# hardware-ble-led-driver-ws2812.net
KiCad netlist of a schematic drawn in EAGLE
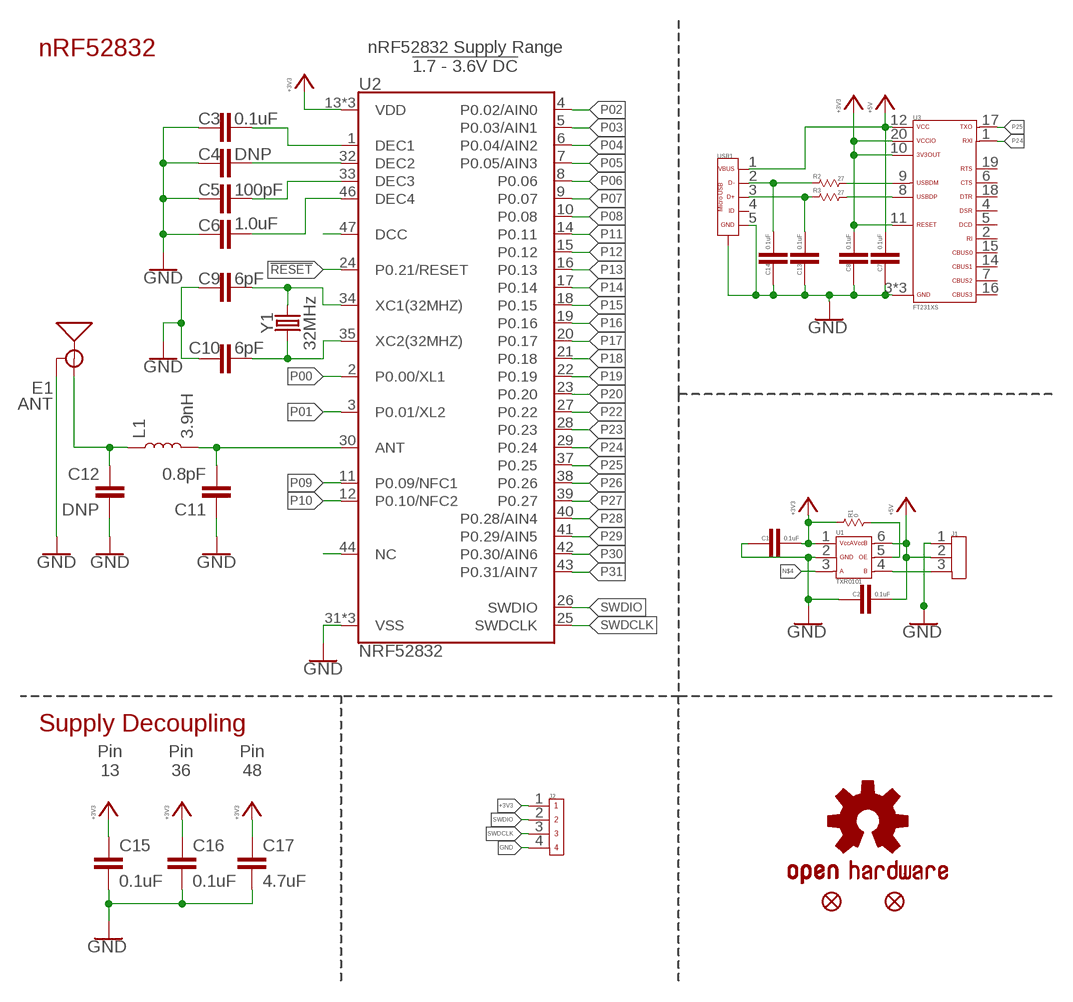
[diagram p0: schematic, sheet 1]

(export (version "E")
  (design (tool "Eeschema 10.0.6"))
  (components
    (comp (ref "C1")
      (value "0.1uF")
      (footprint "eagle-import:0402")
      (libsource (lib "eagle-import") (part "0.1UF-0402-16V-10%"))
    )
    (comp (ref "C2")
      (value "0.1uF")
      (footprint "eagle-import:0402")
      (libsource (lib "eagle-import") (part "0.1UF-0402-16V-10%"))
    )
    (comp (ref "C3")
      (value "0.1uF")
      (footprint "eagle-import:0402")
      (libsource (lib "eagle-import") (part "0.1UF-0402-16V-10%"))
    )
    (comp (ref "C4")
      (value "DNP")
      (footprint "eagle-import:0402")
      (libsource (lib "eagle-import") (part "CAP0402"))
    )
    (comp (ref "C5")
      (value "100pF")
      (footprint "eagle-import:0402")
      (libsource (lib "eagle-import") (part "100PF-0402-50V-5%"))
    )
    (comp (ref "C6")
      (value "1.0uF")
      (footprint "eagle-import:0402")
      (libsource (lib "eagle-import") (part "1.0UF-0402-16V-10%"))
    )
    (comp (ref "C7")
      (value "0.1uF")
      (footprint "eagle-import:0402")
      (libsource (lib "eagle-import") (part "0.1UF-0402-16V-10%"))
    )
    (comp (ref "C8")
      (value "0.1uF")
      (footprint "eagle-import:0402")
      (libsource (lib "eagle-import") (part "0.1UF-0402-16V-10%"))
    )
    (comp (ref "C9")
      (value "6pF")
      (footprint "eagle-import:0402")
      (libsource (lib "eagle-import") (part "6PF-0402-50V-0.5%"))
    )
    (comp (ref "C10")
      (value "6pF")
      (footprint "eagle-import:0402")
      (libsource (lib "eagle-import") (part "6PF-0402-50V-0.5%"))
    )
    (comp (ref "C11")
      (value "0.8pF")
      (footprint "eagle-import:0402")
      (libsource (lib "eagle-import") (part "0.8PF-0402-50V-0.1PF"))
    )
    (comp (ref "C12")
      (value "DNP")
      (footprint "eagle-import:0402")
      (libsource (lib "eagle-import") (part "CAP0402"))
    )
    (comp (ref "C13")
      (value "0.1uF")
      (footprint "eagle-import:0402")
      (libsource (lib "eagle-import") (part "0.1UF-0402-16V-10%"))
    )
    (comp (ref "C14")
      (value "0.1uF")
      (footprint "eagle-import:0402")
      (libsource (lib "eagle-import") (part "0.1UF-0402-16V-10%"))
    )
    (comp (ref "C15")
      (value "0.1uF")
      (footprint "eagle-import:0402")
      (libsource (lib "eagle-import") (part "0.1UF-0402-16V-10%"))
    )
    (comp (ref "C16")
      (value "0.1uF")
      (footprint "eagle-import:0402")
      (libsource (lib "eagle-import") (part "0.1UF-0402-16V-10%"))
    )
    (comp (ref "C17")
      (value "4.7uF")
      (footprint "eagle-import:0603")
      (libsource (lib "eagle-import") (part "4.7UF0603"))
    )
    (comp (ref "E1")
      (value "ANT")
      (footprint "eagle-import:TRACE_ANTENNA_2.4GHZ_15.2MM")
      (libsource (lib "eagle-import") (part "ANTENNA-GROUNDEDTRACE-15.2MM"))
    )
    (comp (ref "FD1")
      (value "FIDUCIALUFIDUCIAL")
      (footprint "eagle-import:FIDUCIAL-MICRO")
      (libsource (lib "eagle-import") (part "FIDUCIALUFIDUCIAL"))
    )
    (comp (ref "FD2")
      (value "FIDUCIALUFIDUCIAL")
      (footprint "eagle-import:FIDUCIAL-MICRO")
      (libsource (lib "eagle-import") (part "FIDUCIALUFIDUCIAL"))
    )
    (comp (ref "J1")
      (value "3PIN_HEADER_PITCH2.54MM_TH")
      (footprint "eagle-import:3PIN_HEADER_PITCH2.54MM_TH")
      (libsource (lib "eagle-import") (part "3PIN_HEADER_PITCH2.54MM_TH"))
    )
    (comp (ref "J2")
      (value "4PIN_HEADER_PITCH1.27MM_TH")
      (footprint "eagle-import:4PIN_HEADER_PITCH1.27MM_TH")
      (libsource (lib "eagle-import") (part "4PIN_HEADER_PITCH1.27MM_TH"))
    )
    (comp (ref "L1")
      (value "3.9nH")
      (footprint "eagle-import:0402")
      (libsource (lib "eagle-import") (part "INDUCTOR-0402-3.9NH"))
    )
    (comp (ref "LOGO1")
      (value "OSHW-LOGOMINI")
      (footprint "eagle-import:OSHW-LOGO-MINI")
      (libsource (lib "eagle-import") (part "OSHW-LOGOMINI"))
    )
    (comp (ref "R1")
      (value "0")
      (footprint "eagle-import:0402")
      (libsource (lib "eagle-import") (part "RESISTOR_0402"))
    )
    (comp (ref "R2")
      (value "27")
      (footprint "eagle-import:0402")
      (libsource (lib "eagle-import") (part "RESISTOR_0402"))
    )
    (comp (ref "R3")
      (value "27")
      (footprint "eagle-import:0402")
      (libsource (lib "eagle-import") (part "RESISTOR_0402"))
    )
    (comp (ref "U1")
      (value "TXB0101-DCK")
      (footprint "eagle-import:TSSOP-6")
      (libsource (lib "eagle-import") (part "TXB0101-DCK"))
    )
    (comp (ref "U2")
      (value "NRF52832")
      (footprint "eagle-import:QFN48-6X6MM")
      (libsource (lib "eagle-import") (part "NRF52832"))
    )
    (comp (ref "U3")
      (value "FT231XS_WFQFN20")
      (footprint "eagle-import:WFQFN-20")
      (libsource (lib "eagle-import") (part "FT231XS_WFQFN20"))
    )
    (comp (ref "USB1")
      (value "USB-2.0-MICRO_SMD_SMD")
      (footprint "eagle-import:MICRO-USB-B-SMD-SMD")
      (libsource (lib "eagle-import") (part "USB-2.0-MICRO_SMD_SMD"))
    )
    (comp (ref "Y1")
      (value "32MHz")
      (footprint "eagle-import:CRYSTAL-SMD-2.0X1.6MM")
      (libsource (lib "eagle-import") (part "CRYSTAL-32MHZ-SMD-2.0X1.6MM"))
    )
  )
  (nets
    (net (code "1") (name "+3V3") (class "Default")
      (node (ref "C1") (pin "2") (pinfunction "2_2") (pintype "passive"))
      (node (ref "C15") (pin "1") (pinfunction "1_1") (pintype "passive"))
      (node (ref "C16") (pin "1") (pinfunction "1_1") (pintype "passive"))
      (node (ref "C17") (pin "1") (pinfunction "1_1") (pintype "passive"))
      (node (ref "C8") (pin "2") (pinfunction "2_2") (pintype "passive"))
      (node (ref "J2") (pin "1") (pinfunction "1_1") (pintype "passive"))
      (node (ref "R1") (pin "1") (pinfunction "1_1") (pintype "passive"))
      (node (ref "U1") (pin "1") (pinfunction "1_1") (pintype "passive"))
      (node (ref "U2") (pin "13") (pinfunction "VDD_13") (pintype "bidirectional"))
      (node (ref "U2") (pin "36") (pinfunction "VDD_36") (pintype "bidirectional"))
      (node (ref "U2") (pin "48") (pinfunction "VDD_48") (pintype "bidirectional"))
      (node (ref "U3") (pin "10") (pinfunction "3V3OUT_10") (pintype "passive"))
      (node (ref "U3") (pin "11") (pinfunction "RESET_11") (pintype "passive"))
      (node (ref "U3") (pin "20") (pinfunction "VCCIO_20") (pintype "passive"))
    )
    (net (code "2") (name "+5V") (class "Default")
      (node (ref "C2") (pin "2") (pinfunction "2_2") (pintype "passive"))
      (node (ref "C7") (pin "2") (pinfunction "2_2") (pintype "passive"))
      (node (ref "J1") (pin "2") (pinfunction "2_2") (pintype "passive"))
      (node (ref "U1") (pin "6") (pinfunction "6_6") (pintype "passive"))
      (node (ref "U3") (pin "12") (pinfunction "VCC_12") (pintype "passive"))
      (node (ref "USB1") (pin "1") (pinfunction "VBUS_1") (pintype "passive"))
    )
    (net (code "3") (name "/~{RESET}") (class "Default")
      (node (ref "U2") (pin "24") (pinfunction "P0.21/RESET_24") (pintype "bidirectional"))
    )
    (net (code "4") (name "GND") (class "Default")
      (node (ref "C1") (pin "1") (pinfunction "1_1") (pintype "passive"))
      (node (ref "C10") (pin "2") (pinfunction "2_2") (pintype "passive"))
      (node (ref "C11") (pin "1") (pinfunction "1_1") (pintype "passive"))
      (node (ref "C12") (pin "2") (pinfunction "2_2") (pintype "passive"))
      (node (ref "C13") (pin "1") (pinfunction "1_1") (pintype "passive"))
      (node (ref "C14") (pin "1") (pinfunction "1_1") (pintype "passive"))
      (node (ref "C15") (pin "2") (pinfunction "2_2") (pintype "passive"))
      (node (ref "C16") (pin "2") (pinfunction "2_2") (pintype "passive"))
      (node (ref "C17") (pin "2") (pinfunction "2_2") (pintype "passive"))
      (node (ref "C2") (pin "1") (pinfunction "1_1") (pintype "passive"))
      (node (ref "C3") (pin "1") (pinfunction "1_1") (pintype "passive"))
      (node (ref "C4") (pin "1") (pinfunction "1_1") (pintype "passive"))
      (node (ref "C5") (pin "1") (pinfunction "1_1") (pintype "passive"))
      (node (ref "C6") (pin "1") (pinfunction "1_1") (pintype "passive"))
      (node (ref "C7") (pin "1") (pinfunction "1_1") (pintype "passive"))
      (node (ref "C8") (pin "1") (pinfunction "1_1") (pintype "passive"))
      (node (ref "C9") (pin "1") (pinfunction "1_1") (pintype "passive"))
      (node (ref "E1") (pin "GND") (pinfunction "GND_GND") (pintype "bidirectional"))
      (node (ref "J1") (pin "1") (pinfunction "1_1") (pintype "passive"))
      (node (ref "J2") (pin "4") (pinfunction "4_4") (pintype "passive"))
      (node (ref "U1") (pin "2") (pinfunction "2_2") (pintype "passive"))
      (node (ref "U2") (pin "31") (pinfunction "VSS_31") (pintype "bidirectional"))
      (node (ref "U2") (pin "45") (pinfunction "VSS_45") (pintype "bidirectional"))
      (node (ref "U2") (pin "EP") (pinfunction "VSS_EP") (pintype "bidirectional"))
      (node (ref "U3") (pin "13") (pinfunction "GND_13") (pintype "passive"))
      (node (ref "U3") (pin "3") (pinfunction "GND_3") (pintype "passive"))
      (node (ref "U3") (pin "T") (pinfunction "GND_T") (pintype "passive"))
      (node (ref "USB1") (pin "5") (pinfunction "GND_5") (pintype "passive"))
      (node (ref "USB1") (pin "M1") (pinfunction "SHIELD_M1") (pintype "passive"))
      (node (ref "USB1") (pin "M2") (pinfunction "SHIELD_M2") (pintype "passive"))
      (node (ref "USB1") (pin "M3") (pinfunction "SHIELD_M3") (pintype "passive"))
      (node (ref "USB1") (pin "M4") (pinfunction "SHIELD_M4") (pintype "passive"))
      (node (ref "USB1") (pin "S1") (pinfunction "SHIELD_S1") (pintype "passive"))
      (node (ref "USB1") (pin "S2") (pinfunction "SHIELD_S2") (pintype "passive"))
    )
    (net (code "5") (name "N$4") (class "Default")
      (node (ref "U1") (pin "3") (pinfunction "3_3") (pintype "passive"))
    )
    (net (code "6") (name "Net-(E1-SIGNAL)") (class "Default")
      (node (ref "C12") (pin "1") (pinfunction "1_1") (pintype "passive"))
      (node (ref "E1") (pin "ANT") (pinfunction "SIGNAL_ANT") (pintype "bidirectional"))
      (node (ref "L1") (pin "1") (pinfunction "1_1") (pintype "passive"))
    )
    (net (code "7") (name "Net-(J1-Pad3)") (class "Default")
      (node (ref "J1") (pin "3") (pinfunction "3_3") (pintype "passive"))
      (node (ref "U1") (pin "4") (pinfunction "4_4") (pintype "passive"))
    )
    (net (code "8") (name "Net-(R1-Pad2)") (class "Default")
      (node (ref "R1") (pin "2") (pinfunction "2_2") (pintype "passive"))
      (node (ref "U1") (pin "5") (pinfunction "5_5") (pintype "passive"))
    )
    (net (code "9") (name "Net-(U2-ANT)") (class "Default")
      (node (ref "C11") (pin "2") (pinfunction "2_2") (pintype "passive"))
      (node (ref "L1") (pin "2") (pinfunction "2_2") (pintype "passive"))
      (node (ref "U2") (pin "30") (pinfunction "ANT_30") (pintype "bidirectional"))
    )
    (net (code "10") (name "Net-(U2-DEC1)") (class "Default")
      (node (ref "C3") (pin "2") (pinfunction "2_2") (pintype "passive"))
      (node (ref "U2") (pin "1") (pinfunction "DEC1_1") (pintype "bidirectional"))
    )
    (net (code "11") (name "Net-(U2-DEC2)") (class "Default")
      (node (ref "C4") (pin "2") (pinfunction "2_2") (pintype "passive"))
      (node (ref "U2") (pin "32") (pinfunction "DEC2_32") (pintype "bidirectional"))
    )
    (net (code "12") (name "Net-(U2-DEC3)") (class "Default")
      (node (ref "C5") (pin "2") (pinfunction "2_2") (pintype "passive"))
      (node (ref "U2") (pin "33") (pinfunction "DEC3_33") (pintype "bidirectional"))
    )
    (net (code "13") (name "Net-(U2-DEC4)") (class "Default")
      (node (ref "C6") (pin "2") (pinfunction "2_2") (pintype "passive"))
      (node (ref "U2") (pin "46") (pinfunction "DEC4_46") (pintype "bidirectional"))
    )
    (net (code "14") (name "Net-(U2-XC1(32MHZ))") (class "Default")
      (node (ref "C9") (pin "2") (pinfunction "2_2") (pintype "passive"))
      (node (ref "U2") (pin "34") (pinfunction "XC1(32MHZ)_34") (pintype "bidirectional"))
      (node (ref "Y1") (pin "3") (pinfunction "2_3") (pintype "passive"))
    )
    (net (code "15") (name "Net-(U2-XC2(32MHZ))") (class "Default")
      (node (ref "C10") (pin "1") (pinfunction "1_1") (pintype "passive"))
      (node (ref "U2") (pin "35") (pinfunction "XC2(32MHZ)_35") (pintype "bidirectional"))
      (node (ref "Y1") (pin "1") (pinfunction "1_1") (pintype "passive"))
    )
    (net (code "16") (name "Net-(U3-USBDM)") (class "Default")
      (node (ref "R2") (pin "2") (pinfunction "2_2") (pintype "passive"))
      (node (ref "U3") (pin "9") (pinfunction "USBDM_9") (pintype "passive"))
    )
    (net (code "17") (name "Net-(U3-USBDP)") (class "Default")
      (node (ref "R3") (pin "2") (pinfunction "2_2") (pintype "passive"))
      (node (ref "U3") (pin "8") (pinfunction "USBDP_8") (pintype "passive"))
    )
    (net (code "18") (name "Net-(USB1-D+)") (class "Default")
      (node (ref "C13") (pin "2") (pinfunction "2_2") (pintype "passive"))
      (node (ref "R3") (pin "1") (pinfunction "1_1") (pintype "passive"))
      (node (ref "USB1") (pin "3") (pinfunction "D+_3") (pintype "passive"))
    )
    (net (code "19") (name "Net-(USB1-D-)") (class "Default")
      (node (ref "C14") (pin "2") (pinfunction "2_2") (pintype "passive"))
      (node (ref "R2") (pin "1") (pinfunction "1_1") (pintype "passive"))
      (node (ref "USB1") (pin "2") (pinfunction "D-_2") (pintype "passive"))
    )
    (net (code "20") (name "P00") (class "Default")
      (node (ref "U2") (pin "2") (pinfunction "P0.00/XL1_2") (pintype "bidirectional"))
    )
    (net (code "21") (name "P01") (class "Default")
      (node (ref "U2") (pin "3") (pinfunction "P0.01/XL2_3") (pintype "bidirectional"))
    )
    (net (code "22") (name "P02") (class "Default")
      (node (ref "U2") (pin "4") (pinfunction "P0.02/AIN0_4") (pintype "bidirectional"))
    )
    (net (code "23") (name "P03") (class "Default")
      (node (ref "U2") (pin "5") (pinfunction "P0.03/AIN1_5") (pintype "bidirectional"))
    )
    (net (code "24") (name "P04") (class "Default")
      (node (ref "U2") (pin "6") (pinfunction "P0.04/AIN2_6") (pintype "bidirectional"))
    )
    (net (code "25") (name "P05") (class "Default")
      (node (ref "U2") (pin "7") (pinfunction "P0.05/AIN3_7") (pintype "bidirectional"))
    )
    (net (code "26") (name "P06") (class "Default")
      (node (ref "U2") (pin "8") (pinfunction "P0.06_8") (pintype "bidirectional"))
    )
    (net (code "27") (name "P07") (class "Default")
      (node (ref "U2") (pin "9") (pinfunction "P0.07_9") (pintype "bidirectional"))
    )
    (net (code "28") (name "P08") (class "Default")
      (node (ref "U2") (pin "10") (pinfunction "P0.08_10") (pintype "bidirectional"))
    )
    (net (code "29") (name "P09") (class "Default")
      (node (ref "U2") (pin "11") (pinfunction "P0.09/NFC1_11") (pintype "bidirectional"))
    )
    (net (code "30") (name "P10") (class "Default")
      (node (ref "U2") (pin "12") (pinfunction "P0.10/NFC2_12") (pintype "bidirectional"))
    )
    (net (code "31") (name "P11") (class "Default")
      (node (ref "U2") (pin "14") (pinfunction "P0.11_14") (pintype "bidirectional"))
    )
    (net (code "32") (name "P12") (class "Default")
      (node (ref "U2") (pin "15") (pinfunction "P0.12_15") (pintype "bidirectional"))
    )
    (net (code "33") (name "P13") (class "Default")
      (node (ref "U2") (pin "16") (pinfunction "P0.13_16") (pintype "bidirectional"))
    )
    (net (code "34") (name "P14") (class "Default")
      (node (ref "U2") (pin "17") (pinfunction "P0.14_17") (pintype "bidirectional"))
    )
    (net (code "35") (name "P15") (class "Default")
      (node (ref "U2") (pin "18") (pinfunction "P0.15_18") (pintype "bidirectional"))
    )
    (net (code "36") (name "P16") (class "Default")
      (node (ref "U2") (pin "19") (pinfunction "P0.16_19") (pintype "bidirectional"))
    )
    (net (code "37") (name "P17") (class "Default")
      (node (ref "U2") (pin "20") (pinfunction "P0.17_20") (pintype "bidirectional"))
    )
    (net (code "38") (name "P18") (class "Default")
      (node (ref "U2") (pin "21") (pinfunction "P0.18_21") (pintype "bidirectional"))
    )
    (net (code "39") (name "P19") (class "Default")
      (node (ref "U2") (pin "22") (pinfunction "P0.19_22") (pintype "bidirectional"))
    )
    (net (code "40") (name "P20") (class "Default")
      (node (ref "U2") (pin "23") (pinfunction "P0.20_23") (pintype "bidirectional"))
    )
    (net (code "41") (name "P22") (class "Default")
      (node (ref "U2") (pin "27") (pinfunction "P0.22_27") (pintype "bidirectional"))
    )
    (net (code "42") (name "P23") (class "Default")
      (node (ref "U2") (pin "28") (pinfunction "P0.23_28") (pintype "bidirectional"))
    )
    (net (code "43") (name "P24") (class "Default")
      (node (ref "U2") (pin "29") (pinfunction "P0.24_29") (pintype "bidirectional"))
      (node (ref "U3") (pin "1") (pinfunction "RXD_1") (pintype "passive"))
    )
    (net (code "44") (name "P25") (class "Default")
      (node (ref "U2") (pin "37") (pinfunction "P0.25_37") (pintype "bidirectional"))
      (node (ref "U3") (pin "17") (pinfunction "TXD_17") (pintype "passive"))
    )
    (net (code "45") (name "P26") (class "Default")
      (node (ref "U2") (pin "38") (pinfunction "P0.26_38") (pintype "bidirectional"))
    )
    (net (code "46") (name "P27") (class "Default")
      (node (ref "U2") (pin "39") (pinfunction "P0.27_39") (pintype "bidirectional"))
    )
    (net (code "47") (name "P28") (class "Default")
      (node (ref "U2") (pin "40") (pinfunction "P0.28/AIN4_40") (pintype "bidirectional"))
    )
    (net (code "48") (name "P29") (class "Default")
      (node (ref "U2") (pin "41") (pinfunction "P0.29/AIN5_41") (pintype "bidirectional"))
    )
    (net (code "49") (name "P30") (class "Default")
      (node (ref "U2") (pin "42") (pinfunction "P0.30/AIN6_42") (pintype "bidirectional"))
    )
    (net (code "50") (name "P31") (class "Default")
      (node (ref "U2") (pin "43") (pinfunction "P0.31/AIN7_43") (pintype "bidirectional"))
    )
    (net (code "51") (name "SWDCLK") (class "Default")
      (node (ref "J2") (pin "3") (pinfunction "3_3") (pintype "passive"))
      (node (ref "U2") (pin "25") (pinfunction "SWDCLK_25") (pintype "bidirectional"))
    )
    (net (code "52") (name "SWDIO") (class "Default")
      (node (ref "J2") (pin "2") (pinfunction "2_2") (pintype "passive"))
      (node (ref "U2") (pin "26") (pinfunction "SWDIO_26") (pintype "bidirectional"))
    )
    (net (code "53") (name "unconnected-(U2-DCC-Pad47)") (class "Default")
      (node (ref "U2") (pin "47") (pinfunction "DCC_47") (pintype "bidirectional"))
    )
    (net (code "54") (name "unconnected-(U2-NC-Pad44)") (class "Default")
      (node (ref "U2") (pin "44") (pinfunction "NC_44") (pintype "bidirectional"))
    )
    (net (code "55") (name "unconnected-(U3-CBUS0-Pad15)") (class "Default")
      (node (ref "U3") (pin "15") (pinfunction "CBUS0_15") (pintype "passive"))
    )
    (net (code "56") (name "unconnected-(U3-CBUS1-Pad14)") (class "Default")
      (node (ref "U3") (pin "14") (pinfunction "CBUS1_14") (pintype "passive"))
    )
    (net (code "57") (name "unconnected-(U3-CBUS2-Pad7)") (class "Default")
      (node (ref "U3") (pin "7") (pinfunction "CBUS2_7") (pintype "passive"))
    )
    (net (code "58") (name "unconnected-(U3-CBUS3-Pad16)") (class "Default")
      (node (ref "U3") (pin "16") (pinfunction "CBUS3_16") (pintype "passive"))
    )
    (net (code "59") (name "unconnected-(U3-CTS-Pad6)") (class "Default")
      (node (ref "U3") (pin "6") (pinfunction "CTS_6") (pintype "passive"))
    )
    (net (code "60") (name "unconnected-(U3-DCD-Pad5)") (class "Default")
      (node (ref "U3") (pin "5") (pinfunction "DCD_5") (pintype "passive"))
    )
    (net (code "61") (name "unconnected-(U3-DSR-Pad4)") (class "Default")
      (node (ref "U3") (pin "4") (pinfunction "DSR_4") (pintype "passive"))
    )
    (net (code "62") (name "unconnected-(U3-DTR-Pad18)") (class "Default")
      (node (ref "U3") (pin "18") (pinfunction "DTR_18") (pintype "passive"))
    )
    (net (code "63") (name "unconnected-(U3-RI-Pad2)") (class "Default")
      (node (ref "U3") (pin "2") (pinfunction "RI_2") (pintype "passive"))
    )
    (net (code "64") (name "unconnected-(U3-RTS-Pad19)") (class "Default")
      (node (ref "U3") (pin "19") (pinfunction "RTS_19") (pintype "passive"))
    )
    (net (code "65") (name "unconnected-(USB1-ID-Pad4)") (class "Default")
      (node (ref "USB1") (pin "4") (pinfunction "ID_4") (pintype "passive"))
    )
  )
)
